# air-quality-wing.net
KiCad netlist of a schematic drawn in EAGLE
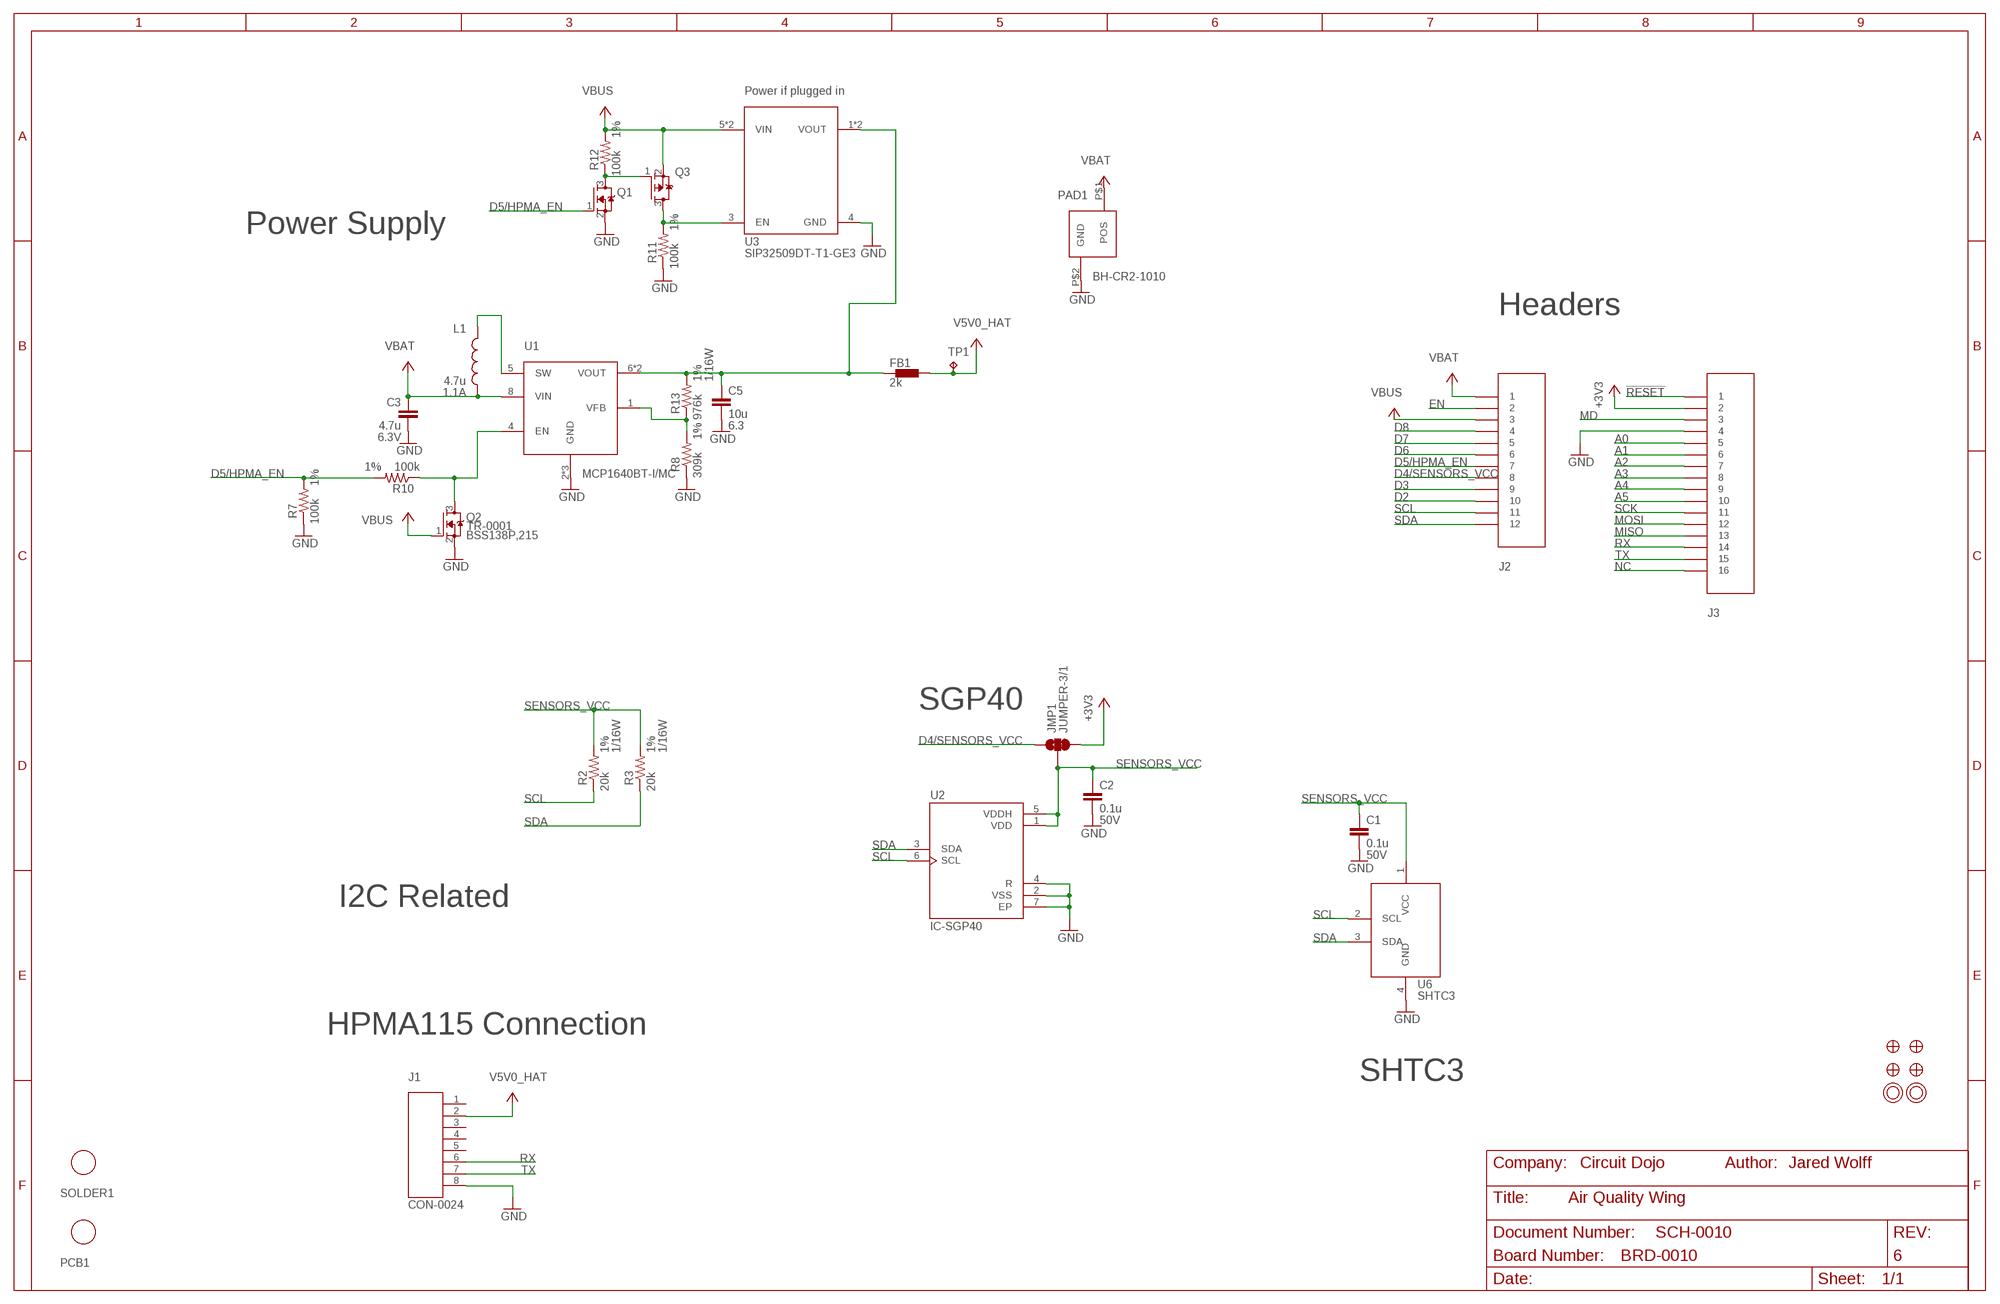
[diagram p0: schematic, sheet 1]

(export (version "E")
  (design (tool "Eeschema 10.0.6"))
  (components
    (comp (ref "C1")
      (value "0.1u")
      (footprint "eagle-import:CAPC1005X55N")
      (fields
        (field (name "MF") "Taiyo Yuden")
        (field (name "MPN") "UMK105BJ104KV-F")
        (field (name "VOLTHIGH") "50V")
      )
      (libsource (lib "eagle-import") (part "CAP-0402-0.1U-50V"))
    )
    (comp (ref "C2")
      (value "0.1u")
      (footprint "eagle-import:CAPC1005X55N")
      (fields
        (field (name "MF") "Taiyo Yuden")
        (field (name "MPN") "UMK105BJ104KV-F")
        (field (name "VOLTHIGH") "50V")
      )
      (libsource (lib "eagle-import") (part "CAP-0402-0.1U-50V"))
    )
    (comp (ref "C3")
      (value "4.7u")
      (footprint "eagle-import:C0603")
      (fields (field (name "MPN") "CL10B475KQ8NQNC") (field (name "VOLTHIGH") "6.3V"))
      (libsource (lib "eagle-import") (part "CAP-0603-4.7U-6.3V"))
    )
    (comp (ref "C5")
      (value "10u")
      (footprint "eagle-import:C0603")
      (fields (field (name "MPN") "JMK107ABJ106MA-T") (field (name "VOLTHIGH") "6.3"))
      (libsource (lib "eagle-import") (part "CAP-0603-10U-6.3V"))
    )
    (comp (ref "FB1")
      (value "2k")
      (footprint "eagle-import:R0805")
      (fields (field (name "MPN") "CIM21J202NE"))
      (libsource (lib "eagle-import") (part "FERRITE-0805"))
    )
    (comp (ref "J1")
      (value "CON-0024")
      (footprint "eagle-import:0532610871")
      (fields (field (name "MPN") "0532610871"))
      (libsource (lib "eagle-import") (part "CON-0024"))
    )
    (comp (ref "J2")
      (value "CON-HEADER-1X12-PPPC121LFBN-RC")
      (footprint "eagle-import:CON-HEADER-1X12")
      (fields (field (name "MF") "Sullins Connector Solutions") (field (name "MPN") "PPPC121LFBN-RC"))
      (libsource (lib "eagle-import") (part "CON-HEADER-1X12-PPPC121LFBN-RC"))
    )
    (comp (ref "J3")
      (value "CON-HEADER-1X16-PPPC161LFBN-RC")
      (footprint "eagle-import:CON-HEADER-1X16")
      (fields (field (name "MF") "Sullins Connector Solutions") (field (name "MPN") "PPPC161LFBN-RC"))
      (libsource (lib "eagle-import") (part "CON-HEADER-1X16-PPPC161LFBN-RC"))
    )
    (comp (ref "JMP1")
      (value "JUMPER-3/1")
      (footprint "eagle-import:JUMPER-ROUND-3-NO-R")
      (libsource (lib "eagle-import") (part "JUMPER-3/1"))
    )
    (comp (ref "L1")
      (value "4.7u")
      (footprint "eagle-import:IND-2P0X2P0X1P2")
      (fields (field (name "CURRENT") "1.1A") (field (name "MPN") "NRV2012T4R7MGF"))
      (libsource (lib "eagle-import") (part "IND-0003"))
    )
    (comp (ref "PAD1")
      (value "BH-CR2-1010")
      (footprint "eagle-import:1010")
      (libsource (lib "eagle-import") (part "BH-1010-CR2"))
    )
    (comp (ref "PCB1")
      (value "PCB-PS-AQW")
      (footprint "eagle-import:PLACEHOLDER")
      (fields (field (name "MPN") "BRD-0010"))
      (libsource (lib "eagle-import") (part "PCB-PS-AQW"))
    )
    (comp (ref "Q1")
      (value "TR-0001")
      (footprint "eagle-import:SOT23")
      (fields (field (name "MPN") "BSS138P,215"))
      (libsource (lib "eagle-import") (part "TR-0001"))
    )
    (comp (ref "Q2")
      (value "TR-0001")
      (footprint "eagle-import:SOT23")
      (fields (field (name "MPN") "BSS138P,215"))
      (libsource (lib "eagle-import") (part "TR-0001"))
    )
    (comp (ref "Q3")
      (value "TR-0003")
      (footprint "eagle-import:SOT23@1")
      (fields (field (name "MPN") "BSS84-7-F"))
      (libsource (lib "eagle-import") (part "TR-0003"))
    )
    (comp (ref "R2")
      (value "20k")
      (footprint "eagle-import:R0402-M")
      (fields
        (field (name "MF") "Yageo")
        (field (name "MPN") "RC0402FR-0720KL")
        (field (name "POWER") "1/16W")
        (field (name "TOLERANCE") "1%")
      )
      (libsource (lib "eagle-import") (part "RES-0402-20K-1%"))
    )
    (comp (ref "R3")
      (value "20k")
      (footprint "eagle-import:R0402-M")
      (fields
        (field (name "MF") "Yageo")
        (field (name "MPN") "RC0402FR-0720KL")
        (field (name "POWER") "1/16W")
        (field (name "TOLERANCE") "1%")
      )
      (libsource (lib "eagle-import") (part "RES-0402-20K-1%"))
    )
    (comp (ref "R7")
      (value "100k")
      (footprint "eagle-import:R0402-M")
      (fields
        (field (name "MPN") "RC0402FR07100KL")
        (field (name "POWER") "1/16W")
        (field (name "TOLERANCE") "1%")
      )
      (libsource (lib "eagle-import") (part "RES-0402-100K-1%"))
    )
    (comp (ref "R8")
      (value "309k")
      (footprint "eagle-import:R0402-M")
      (fields
        (field (name "MPN") "RC0402FR-07309KL")
        (field (name "POWER") "1/16W")
        (field (name "TOLERANCE") "1%")
      )
      (libsource (lib "eagle-import") (part "RES-0402-309K-1%"))
    )
    (comp (ref "R10")
      (value "100k")
      (footprint "eagle-import:R0402-M")
      (fields
        (field (name "MPN") "RC0402FR07100KL")
        (field (name "POWER") "1/16W")
        (field (name "TOLERANCE") "1%")
      )
      (libsource (lib "eagle-import") (part "RES-0402-100K-1%"))
    )
    (comp (ref "R11")
      (value "100k")
      (footprint "eagle-import:R0402-M")
      (fields
        (field (name "MPN") "RC0402FR07100KL")
        (field (name "POWER") "1/16W")
        (field (name "TOLERANCE") "1%")
      )
      (libsource (lib "eagle-import") (part "RES-0402-100K-1%"))
    )
    (comp (ref "R12")
      (value "100k")
      (footprint "eagle-import:R0402-M")
      (fields
        (field (name "MPN") "RC0402FR07100KL")
        (field (name "POWER") "1/16W")
        (field (name "TOLERANCE") "1%")
      )
      (libsource (lib "eagle-import") (part "RES-0402-100K-1%"))
    )
    (comp (ref "R13")
      (value "976k")
      (footprint "eagle-import:R0402-M")
      (fields
        (field (name "MF") "Yageo")
        (field (name "MPN") "RC0402FR-07976KL")
        (field (name "POWER") "1/16W")
        (field (name "TOLERANCE") "1%")
      )
      (libsource (lib "eagle-import") (part "RES-0402-976K-1%"))
    )
    (comp (ref "SOLDER1")
      (value "SOLDER")
      (footprint "eagle-import:PLACEHOLDER")
      (fields (field (name "MPN") "TS391SNL50"))
      (libsource (lib "eagle-import") (part "SOLDER-PASTE-ROOM-TEMP-50G"))
    )
    (comp (ref "TP1")
      (value "TP")
      (footprint "eagle-import:TP-1P27")
      (libsource (lib "eagle-import") (part "TP"))
    )
    (comp (ref "U$3")
      (value "FIDUCIAL-1MM")
      (footprint "eagle-import:FIDUCIAL-1MM")
      (libsource (lib "eagle-import") (part "FIDUCIAL-1MM"))
    )
    (comp (ref "U$4")
      (value "FIDUCIAL-1MM")
      (footprint "eagle-import:FIDUCIAL-1MM")
      (libsource (lib "eagle-import") (part "FIDUCIAL-1MM"))
    )
    (comp (ref "U$31")
      (value "MOUNTING-HOLE-2.5MM-PLATED")
      (footprint "eagle-import:MOUNTING-HOLE-2.5MM-PLATED")
      (libsource (lib "eagle-import") (part "MOUNTING-HOLE-2.5MM-PLATED"))
    )
    (comp (ref "U$32")
      (value "MOUNTING-HOLE-2.5MM-PLATED")
      (footprint "eagle-import:MOUNTING-HOLE-2.5MM-PLATED")
      (libsource (lib "eagle-import") (part "MOUNTING-HOLE-2.5MM-PLATED"))
    )
    (comp (ref "U$34")
      (value "FIDUCIAL-1MM")
      (footprint "eagle-import:FIDUCIAL-1MM")
      (libsource (lib "eagle-import") (part "FIDUCIAL-1MM"))
    )
    (comp (ref "U$35")
      (value "FIDUCIAL-1MM")
      (footprint "eagle-import:FIDUCIAL-1MM")
      (libsource (lib "eagle-import") (part "FIDUCIAL-1MM"))
    )
    (comp (ref "U1")
      (value "POWER-VREG-FB-EN-SW-350MA-DFN8")
      (footprint "eagle-import:DFN200X300X100-9N")
      (fields (field (name "MF") "Microchip Technology") (field (name "MPN") "MCP1640BT-I/MC"))
      (libsource (lib "eagle-import") (part "POWER-VREG-FB-EN-SW-DFN8-350MA"))
    )
    (comp (ref "U2")
      (value "IC-SGP40")
      (footprint "eagle-import:XDCR_SGP30-2.5K")
      (fields (field (name "MF") "Sensirion AG") (field (name "MPN") "SGP40-D-R4"))
      (libsource (lib "eagle-import") (part "IC-SGP40"))
    )
    (comp (ref "U3")
      (value "POWER-SWITCH-SIP32509-SO23-6")
      (footprint "eagle-import:SOT23-6")
      (fields (field (name "MPN") "SIP32509DT-T1-GE3"))
      (libsource (lib "eagle-import") (part "POWER-SWITCH-SO23-6-SIP32509"))
    )
    (comp (ref "U6")
      (value "IC-SHTC3")
      (footprint "eagle-import:IC-SHTC3")
      (fields (field (name "MPN") "SHTC3") (field (name "MF") "SENSIRION"))
      (libsource (lib "eagle-import") (part "IC-SHTC3"))
    )
  )
  (nets
    (net (code "1") (name "+3V3") (class "Default")
      (node (ref "J3") (pin "2") (pinfunction "2_2") (pintype "bidirectional"))
      (node (ref "JMP1") (pin "P$3") (pinfunction "3_P$3") (pintype "passive"))
    )
    (net (code "2") (name "/A0") (class "Default")
      (node (ref "J3") (pin "5") (pinfunction "5_5") (pintype "bidirectional"))
    )
    (net (code "3") (name "/A1") (class "Default")
      (node (ref "J3") (pin "6") (pinfunction "6_6") (pintype "bidirectional"))
    )
    (net (code "4") (name "/A2") (class "Default")
      (node (ref "J3") (pin "7") (pinfunction "7_7") (pintype "bidirectional"))
    )
    (net (code "5") (name "/A3") (class "Default")
      (node (ref "J3") (pin "8") (pinfunction "8_8") (pintype "bidirectional"))
    )
    (net (code "6") (name "/A4") (class "Default")
      (node (ref "J3") (pin "9") (pinfunction "9_9") (pintype "bidirectional"))
    )
    (net (code "7") (name "/A5") (class "Default")
      (node (ref "J3") (pin "10") (pinfunction "10_10") (pintype "bidirectional"))
    )
    (net (code "8") (name "/D2") (class "Default")
      (node (ref "J2") (pin "10") (pinfunction "10_10") (pintype "bidirectional"))
    )
    (net (code "9") (name "/D3") (class "Default")
      (node (ref "J2") (pin "9") (pinfunction "9_9") (pintype "bidirectional"))
    )
    (net (code "10") (name "/D4{slash}SENSORS_VCC") (class "Default")
      (node (ref "J2") (pin "8") (pinfunction "8_8") (pintype "bidirectional"))
      (node (ref "JMP1") (pin "P$1") (pinfunction "1_P$1") (pintype "passive"))
    )
    (net (code "11") (name "/D5{slash}HPMA_EN") (class "Default")
      (node (ref "J2") (pin "7") (pinfunction "7_7") (pintype "bidirectional"))
      (node (ref "Q1") (pin "1") (pinfunction "G_1") (pintype "bidirectional"))
      (node (ref "R10") (pin "2") (pinfunction "2_2") (pintype "passive"))
      (node (ref "R7") (pin "2") (pinfunction "2_2") (pintype "passive"))
    )
    (net (code "12") (name "/D6") (class "Default")
      (node (ref "J2") (pin "6") (pinfunction "6_6") (pintype "bidirectional"))
    )
    (net (code "13") (name "/D7") (class "Default")
      (node (ref "J2") (pin "5") (pinfunction "5_5") (pintype "bidirectional"))
    )
    (net (code "14") (name "/D8") (class "Default")
      (node (ref "J2") (pin "4") (pinfunction "4_4") (pintype "bidirectional"))
    )
    (net (code "15") (name "/EN") (class "Default")
      (node (ref "J2") (pin "2") (pinfunction "2_2") (pintype "bidirectional"))
    )
    (net (code "16") (name "/MD") (class "Default")
      (node (ref "J3") (pin "3") (pinfunction "3_3") (pintype "bidirectional"))
    )
    (net (code "17") (name "/MISO") (class "Default")
      (node (ref "J3") (pin "13") (pinfunction "13_13") (pintype "bidirectional"))
    )
    (net (code "18") (name "/MOSI") (class "Default")
      (node (ref "J3") (pin "12") (pinfunction "12_12") (pintype "bidirectional"))
    )
    (net (code "19") (name "/NC") (class "Default")
      (node (ref "J3") (pin "16") (pinfunction "16_16") (pintype "bidirectional"))
    )
    (net (code "20") (name "/RX") (class "Default")
      (node (ref "J1") (pin "6") (pinfunction "P$6_6") (pintype "bidirectional"))
      (node (ref "J3") (pin "14") (pinfunction "14_14") (pintype "bidirectional"))
    )
    (net (code "21") (name "/SCK") (class "Default")
      (node (ref "J3") (pin "11") (pinfunction "11_11") (pintype "bidirectional"))
    )
    (net (code "22") (name "/SCL") (class "Default")
      (node (ref "J2") (pin "11") (pinfunction "11_11") (pintype "bidirectional"))
      (node (ref "R2") (pin "1") (pinfunction "1_1") (pintype "passive"))
      (node (ref "U2") (pin "6") (pinfunction "SCL_6") (pintype "bidirectional"))
      (node (ref "U6") (pin "2") (pinfunction "SCL_2") (pintype "bidirectional"))
    )
    (net (code "23") (name "/SDA") (class "Default")
      (node (ref "J2") (pin "12") (pinfunction "12_12") (pintype "bidirectional"))
      (node (ref "R3") (pin "1") (pinfunction "1_1") (pintype "passive"))
      (node (ref "U2") (pin "3") (pinfunction "SDA_3") (pintype "bidirectional"))
      (node (ref "U6") (pin "3") (pinfunction "SDA_3") (pintype "bidirectional"))
    )
    (net (code "24") (name "/SENSORS_VCC") (class "Default")
      (node (ref "C1") (pin "1") (pinfunction "1_1") (pintype "passive"))
      (node (ref "C2") (pin "1") (pinfunction "1_1") (pintype "passive"))
      (node (ref "JMP1") (pin "P$2") (pinfunction "2_P$2") (pintype "passive"))
      (node (ref "R2") (pin "2") (pinfunction "2_2") (pintype "passive"))
      (node (ref "R3") (pin "2") (pinfunction "2_2") (pintype "passive"))
      (node (ref "U2") (pin "1") (pinfunction "VDD_1") (pintype "power_in"))
      (node (ref "U2") (pin "5") (pinfunction "VDDH_5") (pintype "power_in"))
      (node (ref "U6") (pin "1") (pinfunction "VCC_1") (pintype "bidirectional"))
    )
    (net (code "25") (name "/TX") (class "Default")
      (node (ref "J1") (pin "7") (pinfunction "P$7_7") (pintype "bidirectional"))
      (node (ref "J3") (pin "15") (pinfunction "15_15") (pintype "bidirectional"))
    )
    (net (code "26") (name "/~{RESET}") (class "Default")
      (node (ref "J3") (pin "1") (pinfunction "1_1") (pintype "bidirectional"))
    )
    (net (code "27") (name "GND") (class "Default")
      (node (ref "C1") (pin "2") (pinfunction "2_2") (pintype "passive"))
      (node (ref "C2") (pin "2") (pinfunction "2_2") (pintype "passive"))
      (node (ref "C3") (pin "2") (pinfunction "2_2") (pintype "passive"))
      (node (ref "C5") (pin "2") (pinfunction "2_2") (pintype "passive"))
      (node (ref "J1") (pin "8") (pinfunction "P$8_8") (pintype "bidirectional"))
      (node (ref "J3") (pin "4") (pinfunction "4_4") (pintype "bidirectional"))
      (node (ref "PAD1") (pin "P$2") (pinfunction "GND_P$2") (pintype "power_in"))
      (node (ref "Q1") (pin "2") (pinfunction "S_2") (pintype "bidirectional"))
      (node (ref "Q2") (pin "2") (pinfunction "S_2") (pintype "bidirectional"))
      (node (ref "R11") (pin "1") (pinfunction "1_1") (pintype "passive"))
      (node (ref "R7") (pin "1") (pinfunction "1_1") (pintype "passive"))
      (node (ref "R8") (pin "1") (pinfunction "1_1") (pintype "passive"))
      (node (ref "U1") (pin "2") (pinfunction "GND_2") (pintype "bidirectional"))
      (node (ref "U1") (pin "3") (pinfunction "GND_3") (pintype "bidirectional"))
      (node (ref "U1") (pin "9") (pinfunction "GND_9") (pintype "bidirectional"))
      (node (ref "U2") (pin "2") (pinfunction "VSS_2") (pintype "power_in"))
      (node (ref "U2") (pin "4") (pinfunction "R_4") (pintype "passive"))
      (node (ref "U2") (pin "7") (pinfunction "EP_7") (pintype "power_in"))
      (node (ref "U3") (pin "4") (pinfunction "GND_4") (pintype "power_in"))
      (node (ref "U6") (pin "4") (pinfunction "GND_4") (pintype "bidirectional"))
    )
    (net (code "28") (name "Net-(C5-Pad1)") (class "Default")
      (node (ref "C5") (pin "1") (pinfunction "1_1") (pintype "passive"))
      (node (ref "FB1") (pin "1") (pinfunction "1_1") (pintype "passive"))
      (node (ref "R13") (pin "2") (pinfunction "2_2") (pintype "passive"))
      (node (ref "U1") (pin "6") (pinfunction "VOUT_6") (pintype "bidirectional"))
      (node (ref "U1") (pin "7") (pinfunction "VOUT_7") (pintype "bidirectional"))
      (node (ref "U3") (pin "1") (pinfunction "VOUT_1") (pintype "power_in"))
      (node (ref "U3") (pin "2") (pinfunction "VOUT_2") (pintype "power_in"))
    )
    (net (code "29") (name "Net-(L1-1)") (class "Default")
      (node (ref "L1") (pin "P$1") (pinfunction "1_P$1") (pintype "passive"))
      (node (ref "U1") (pin "5") (pinfunction "SW_5") (pintype "bidirectional"))
    )
    (net (code "30") (name "Net-(Q1-D)") (class "Default")
      (node (ref "Q1") (pin "3") (pinfunction "D_3") (pintype "bidirectional"))
      (node (ref "Q3") (pin "1") (pinfunction "G_1") (pintype "passive"))
      (node (ref "R12") (pin "1") (pinfunction "1_1") (pintype "passive"))
    )
    (net (code "31") (name "Net-(Q2-D)") (class "Default")
      (node (ref "Q2") (pin "3") (pinfunction "D_3") (pintype "bidirectional"))
      (node (ref "R10") (pin "1") (pinfunction "1_1") (pintype "passive"))
      (node (ref "U1") (pin "4") (pinfunction "EN_4") (pintype "bidirectional"))
    )
    (net (code "32") (name "Net-(Q3-D)") (class "Default")
      (node (ref "Q3") (pin "3") (pinfunction "D_3") (pintype "passive"))
      (node (ref "R11") (pin "2") (pinfunction "2_2") (pintype "passive"))
      (node (ref "U3") (pin "3") (pinfunction "EN_3") (pintype "input"))
    )
    (net (code "33") (name "Net-(U1-VFB)") (class "Default")
      (node (ref "R13") (pin "1") (pinfunction "1_1") (pintype "passive"))
      (node (ref "R8") (pin "2") (pinfunction "2_2") (pintype "passive"))
      (node (ref "U1") (pin "1") (pinfunction "VFB_1") (pintype "bidirectional"))
    )
    (net (code "34") (name "V5V0_HAT") (class "Default")
      (node (ref "FB1") (pin "2") (pinfunction "2_2") (pintype "passive"))
      (node (ref "J1") (pin "2") (pinfunction "P$2_2") (pintype "bidirectional"))
      (node (ref "TP1") (pin "P$1") (pinfunction "TP_P$1") (pintype "input"))
      (node (ref "TP1") (pin "P$2") (pinfunction "TP_P$2") (pintype "input"))
      (node (ref "TP1") (pin "TP") (pinfunction "TP_TP") (pintype "input"))
    )
    (net (code "35") (name "VBAT") (class "Default")
      (node (ref "C3") (pin "1") (pinfunction "1_1") (pintype "passive"))
      (node (ref "J2") (pin "1") (pinfunction "1_1") (pintype "bidirectional"))
      (node (ref "L1") (pin "P$2") (pinfunction "2_P$2") (pintype "passive"))
      (node (ref "PAD1") (pin "P$1") (pinfunction "POS_P$1") (pintype "power_in"))
      (node (ref "U1") (pin "8") (pinfunction "VIN_8") (pintype "bidirectional"))
    )
    (net (code "36") (name "VBUS") (class "Default")
      (node (ref "J2") (pin "3") (pinfunction "3_3") (pintype "bidirectional"))
      (node (ref "Q2") (pin "1") (pinfunction "G_1") (pintype "bidirectional"))
      (node (ref "Q3") (pin "2") (pinfunction "S_2") (pintype "passive"))
      (node (ref "R12") (pin "2") (pinfunction "2_2") (pintype "passive"))
      (node (ref "U3") (pin "5") (pinfunction "VIN_5") (pintype "power_in"))
      (node (ref "U3") (pin "6") (pinfunction "VIN_6") (pintype "power_in"))
    )
    (net (code "37") (name "unconnected-(J1-P$1-Pad1)") (class "Default")
      (node (ref "J1") (pin "1") (pinfunction "P$1_1") (pintype "bidirectional"))
    )
    (net (code "38") (name "unconnected-(J1-P$3-Pad3)") (class "Default")
      (node (ref "J1") (pin "3") (pinfunction "P$3_3") (pintype "bidirectional"))
    )
    (net (code "39") (name "unconnected-(J1-P$4-Pad4)") (class "Default")
      (node (ref "J1") (pin "4") (pinfunction "P$4_4") (pintype "bidirectional"))
    )
    (net (code "40") (name "unconnected-(J1-P$5-Pad5)") (class "Default")
      (node (ref "J1") (pin "5") (pinfunction "P$5_5") (pintype "bidirectional"))
    )
  )
)
